# ISPbreadboardAdapter_ATmega328compatible.net
KiCad netlist of a schematic drawn in EAGLE
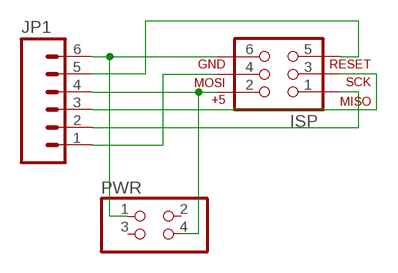
[diagram p0: schematic, sheet 1]

(export (version "E")
  (design (tool "Eeschema 10.0.6"))
  (components
    (comp (ref "ISP")
      (value "AVR_SPI_PRG_6PTH")
      (footprint "eagle-import:2X3")
      (libsource (lib "eagle-import") (part "AVR_SPI_PRG_6PTH"))
    )
    (comp (ref "JP1")
      (value "M06SILK_FEMALE_PTH")
      (footprint "eagle-import:1X06")
      (libsource (lib "eagle-import") (part "M06SILK_FEMALE_PTH"))
    )
    (comp (ref "PWR")
      (value "PINHD-2X2")
      (footprint "eagle-import:2X02")
      (libsource (lib "eagle-import") (part "PINHD-2X2"))
    )
  )
  (nets
    (net (code "1") (name "Net-(ISP-Pad1)") (class "Default")
      (node (ref "ISP") (pin "1") (pinfunction "1_1") (pintype "passive"))
      (node (ref "JP1") (pin "2") (pinfunction "2_2") (pintype "passive"))
    )
    (net (code "2") (name "Net-(ISP-Pad2)") (class "Default")
      (node (ref "ISP") (pin "2") (pinfunction "2_2") (pintype "passive"))
      (node (ref "JP1") (pin "4") (pinfunction "4_4") (pintype "passive"))
      (node (ref "PWR") (pin "4") (pinfunction "4_4") (pintype "passive"))
    )
    (net (code "3") (name "Net-(ISP-Pad3)") (class "Default")
      (node (ref "ISP") (pin "3") (pinfunction "3_3") (pintype "passive"))
      (node (ref "JP1") (pin "3") (pinfunction "3_3") (pintype "passive"))
    )
    (net (code "4") (name "Net-(ISP-Pad4)") (class "Default")
      (node (ref "ISP") (pin "4") (pinfunction "4_4") (pintype "passive"))
      (node (ref "JP1") (pin "1") (pinfunction "1_1") (pintype "passive"))
    )
    (net (code "5") (name "Net-(ISP-Pad5)") (class "Default")
      (node (ref "ISP") (pin "5") (pinfunction "5_5") (pintype "passive"))
      (node (ref "JP1") (pin "5") (pinfunction "5_5") (pintype "passive"))
    )
    (net (code "6") (name "Net-(ISP-Pad6)") (class "Default")
      (node (ref "ISP") (pin "6") (pinfunction "6_6") (pintype "passive"))
      (node (ref "JP1") (pin "6") (pinfunction "6_6") (pintype "passive"))
      (node (ref "PWR") (pin "1") (pinfunction "1_1") (pintype "passive"))
    )
    (net (code "7") (name "unconnected-(PWR-Pad2)") (class "Default")
      (node (ref "PWR") (pin "2") (pinfunction "2_2") (pintype "passive"))
    )
    (net (code "8") (name "unconnected-(PWR-Pad3)") (class "Default")
      (node (ref "PWR") (pin "3") (pinfunction "3_3") (pintype "passive"))
    )
  )
)
